# Adafruit_MCP3421_ADC.net
KiCad netlist of a schematic drawn in EAGLE
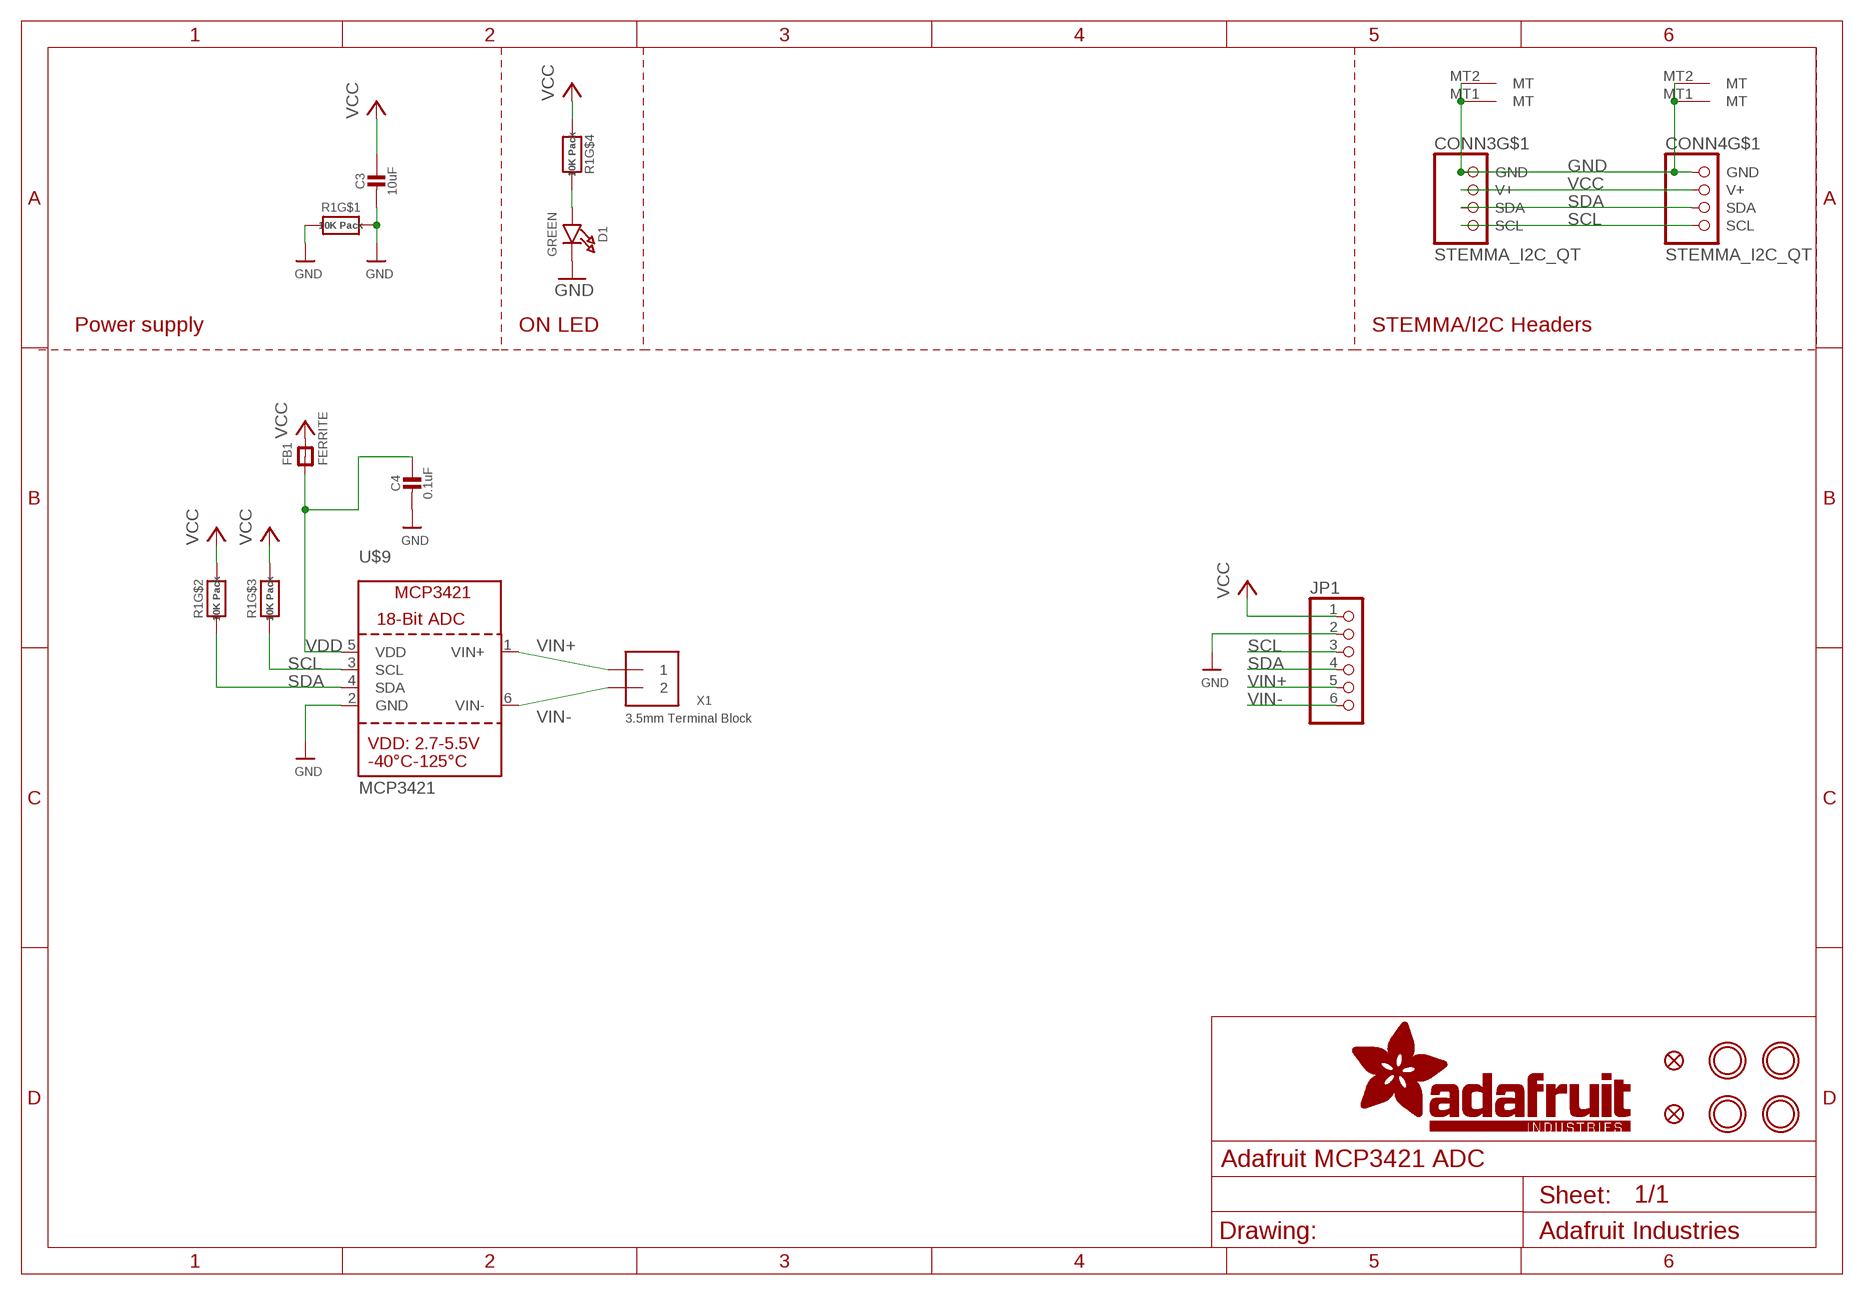
[diagram p0: schematic, sheet 1]

(export (version "E")
  (design (tool "Eeschema 10.0.6"))
  (components
    (comp (ref "C3")
      (value "10uF")
      (footprint "eagle-import:0805-NO")
      (libsource (lib "eagle-import") (part "CAP_CERAMIC0805-NOOUTLINE"))
    )
    (comp (ref "C4")
      (value "0.1uF")
      (footprint "eagle-import:0603-NO")
      (libsource (lib "eagle-import") (part "CAP_CERAMIC0603_NO"))
    )
    (comp (ref "CONN3")
      (value "STEMMA_I2C_QT")
      (footprint "eagle-import:JST_SH4")
      (libsource (lib "eagle-import") (part "STEMMA_I2C_QT"))
    )
    (comp (ref "CONN4")
      (value "STEMMA_I2C_QT")
      (footprint "eagle-import:JST_SH4")
      (libsource (lib "eagle-import") (part "STEMMA_I2C_QT"))
    )
    (comp (ref "D1")
      (value "GREEN")
      (footprint "eagle-import:CHIPLED_0603_NOOUTLINE")
      (libsource (lib "eagle-import") (part "LED0603_NOOUTLINE"))
    )
    (comp (ref "FB1")
      (value "FERRITE")
      (footprint "eagle-import:0603-NO")
      (libsource (lib "eagle-import") (part "FERRITE-0603NO"))
    )
    (comp (ref "FID3")
      (value "FIDUCIAL_1MM")
      (footprint "eagle-import:FIDUCIAL_1MM")
      (libsource (lib "eagle-import") (part "FIDUCIAL_1MM"))
    )
    (comp (ref "FID4")
      (value "FIDUCIAL_1MM")
      (footprint "eagle-import:FIDUCIAL_1MM")
      (libsource (lib "eagle-import") (part "FIDUCIAL_1MM"))
    )
    (comp (ref "JP1")
      (value "HEADER-1X670MIL")
      (footprint "eagle-import:1X06_ROUND_70")
      (libsource (lib "eagle-import") (part "HEADER-1X670MIL"))
    )
    (comp (ref "R1")
      (value "10K Pack")
      (footprint "eagle-import:RESPACK_4X0603")
      (libsource (lib "eagle-import") (part "RESISTOR_4PACK"))
    )
    (comp (ref "U$9")
      (value "MCP3421")
      (footprint "eagle-import:SOT23-6")
      (libsource (lib "eagle-import") (part "MCP3421"))
    )
    (comp (ref "U$20")
      (value "MOUNTINGHOLE2.5")
      (footprint "eagle-import:MOUNTINGHOLE_2.5_PLATED")
      (libsource (lib "eagle-import") (part "MOUNTINGHOLE2.5"))
    )
    (comp (ref "U$21")
      (value "MOUNTINGHOLE2.5")
      (footprint "eagle-import:MOUNTINGHOLE_2.5_PLATED")
      (libsource (lib "eagle-import") (part "MOUNTINGHOLE2.5"))
    )
    (comp (ref "U$25")
      (value "MOUNTINGHOLE2.5")
      (footprint "eagle-import:MOUNTINGHOLE_2.5_PLATED")
      (libsource (lib "eagle-import") (part "MOUNTINGHOLE2.5"))
    )
    (comp (ref "U$27")
      (value "MOUNTINGHOLE2.5")
      (footprint "eagle-import:MOUNTINGHOLE_2.5_PLATED")
      (libsource (lib "eagle-import") (part "MOUNTINGHOLE2.5"))
    )
    (comp (ref "X1")
      (value "3.5mm Terminal Block")
      (footprint "eagle-import:TERMBLOCK_1X2-3.5MM")
      (libsource (lib "eagle-import") (part "TERMBLOCK_1X2_3.5MM"))
    )
  )
  (nets
    (net (code "1") (name "/SCL") (class "Default")
      (node (ref "CONN3") (pin "4") (pinfunction "SCL_4") (pintype "passive"))
      (node (ref "CONN4") (pin "4") (pinfunction "SCL_4") (pintype "passive"))
      (node (ref "JP1") (pin "3") (pinfunction "3_3") (pintype "passive"))
      (node (ref "R1") (pin "3") (pinfunction "1_3") (pintype "passive"))
      (node (ref "U$9") (pin "3") (pinfunction "SCL_3") (pintype "bidirectional"))
    )
    (net (code "2") (name "/SDA") (class "Default")
      (node (ref "CONN3") (pin "3") (pinfunction "SDA_3") (pintype "passive"))
      (node (ref "CONN4") (pin "3") (pinfunction "SDA_3") (pintype "passive"))
      (node (ref "JP1") (pin "4") (pinfunction "4_4") (pintype "passive"))
      (node (ref "R1") (pin "2") (pinfunction "1_2") (pintype "passive"))
      (node (ref "U$9") (pin "4") (pinfunction "SDA_4") (pintype "bidirectional"))
    )
    (net (code "3") (name "/VDD") (class "Default")
      (node (ref "C4") (pin "1") (pinfunction "1_1") (pintype "passive"))
      (node (ref "FB1") (pin "1") (pinfunction "P$1_1") (pintype "passive"))
      (node (ref "U$9") (pin "5") (pinfunction "VDD_5") (pintype "power_in"))
    )
    (net (code "4") (name "/VIN+") (class "Default")
      (node (ref "JP1") (pin "5") (pinfunction "5_5") (pintype "passive"))
      (node (ref "U$9") (pin "1") (pinfunction "VIN+_1") (pintype "output"))
      (node (ref "X1") (pin "1") (pinfunction "1_1") (pintype "passive"))
    )
    (net (code "5") (name "/VIN-") (class "Default")
      (node (ref "JP1") (pin "6") (pinfunction "6_6") (pintype "passive"))
      (node (ref "U$9") (pin "6") (pinfunction "VIN-_6") (pintype "input"))
      (node (ref "X1") (pin "2") (pinfunction "2_2") (pintype "passive"))
    )
    (net (code "6") (name "GND") (class "Default")
      (node (ref "C3") (pin "2") (pinfunction "2_2") (pintype "passive"))
      (node (ref "C4") (pin "2") (pinfunction "2_2") (pintype "passive"))
      (node (ref "CONN3") (pin "1") (pinfunction "GND_1") (pintype "passive"))
      (node (ref "CONN3") (pin "MT1") (pinfunction "MT_MT1") (pintype "bidirectional"))
      (node (ref "CONN3") (pin "MT2") (pinfunction "MT_MT2") (pintype "bidirectional"))
      (node (ref "CONN4") (pin "1") (pinfunction "GND_1") (pintype "passive"))
      (node (ref "CONN4") (pin "MT1") (pinfunction "MT_MT1") (pintype "bidirectional"))
      (node (ref "CONN4") (pin "MT2") (pinfunction "MT_MT2") (pintype "bidirectional"))
      (node (ref "D1") (pin "C") (pinfunction "C_C") (pintype "passive"))
      (node (ref "JP1") (pin "2") (pinfunction "2_2") (pintype "passive"))
      (node (ref "R1") (pin "1") (pinfunction "1_1") (pintype "passive"))
      (node (ref "R1") (pin "8") (pinfunction "2_8") (pintype "passive"))
      (node (ref "U$9") (pin "2") (pinfunction "GND_2") (pintype "power_in"))
    )
    (net (code "7") (name "Net-(R1D-2)") (class "Default")
      (node (ref "D1") (pin "A") (pinfunction "A_A") (pintype "passive"))
      (node (ref "R1") (pin "5") (pinfunction "2_5") (pintype "passive"))
    )
    (net (code "8") (name "VCC") (class "Default")
      (node (ref "C3") (pin "1") (pinfunction "1_1") (pintype "passive"))
      (node (ref "CONN3") (pin "2") (pinfunction "V+_2") (pintype "passive"))
      (node (ref "CONN4") (pin "2") (pinfunction "V+_2") (pintype "passive"))
      (node (ref "FB1") (pin "2") (pinfunction "P$2_2") (pintype "passive"))
      (node (ref "JP1") (pin "1") (pinfunction "1_1") (pintype "passive"))
      (node (ref "R1") (pin "4") (pinfunction "1_4") (pintype "passive"))
      (node (ref "R1") (pin "6") (pinfunction "2_6") (pintype "passive"))
      (node (ref "R1") (pin "7") (pinfunction "2_7") (pintype "passive"))
    )
  )
)
